# Exoskeleton_PCB_v2.net
KiCad netlist of a schematic drawn in EAGLE
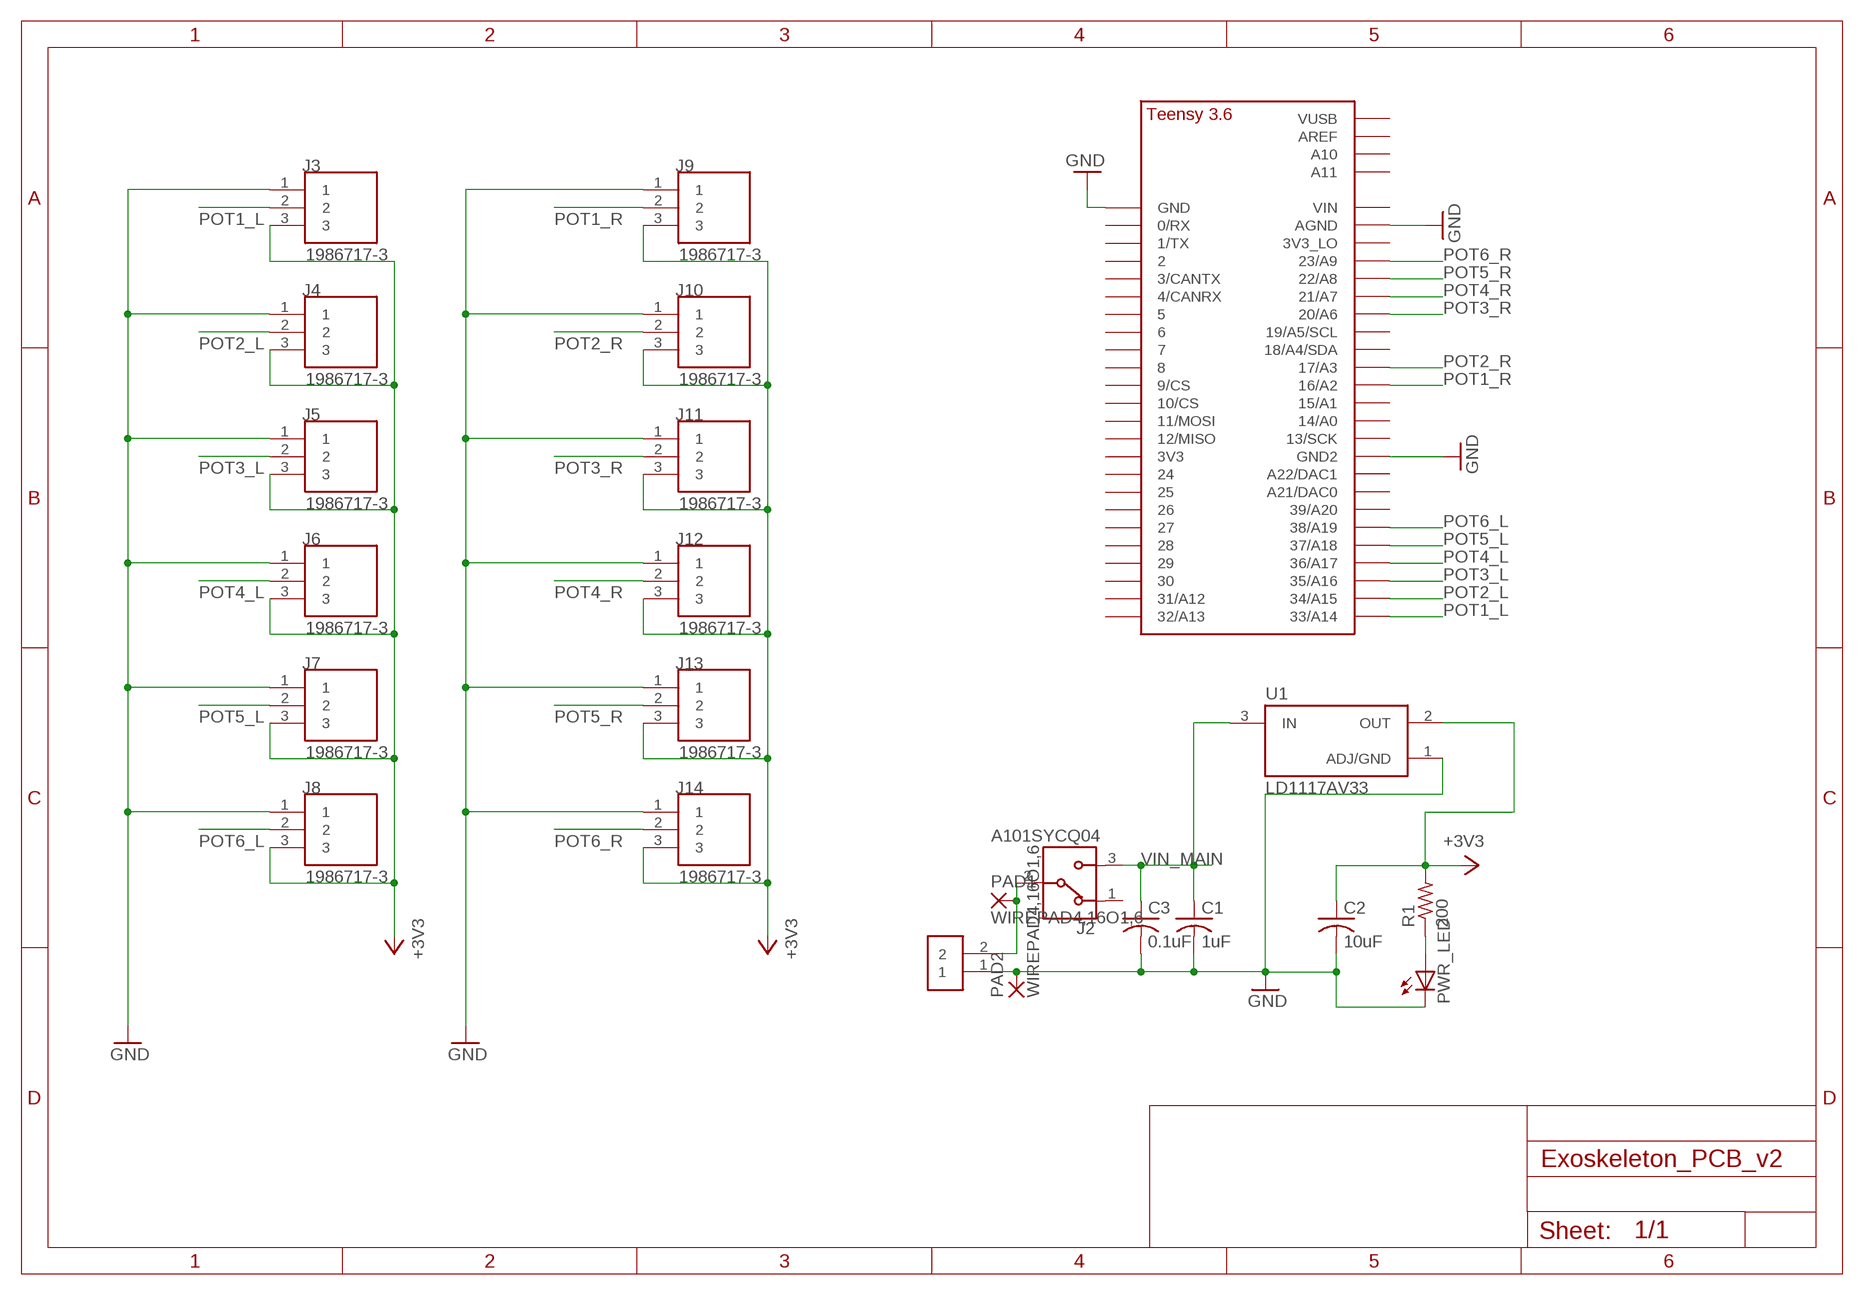
[diagram p0: schematic, sheet 1]

(export (version "E")
  (design (tool "Eeschema 10.0.6"))
  (components
    (comp (ref "C1")
      (value "1uF")
      (footprint "eagle-import:C050-030X075")
      (libsource (lib "eagle-import") (part "C-US050-030X075"))
    )
    (comp (ref "C2")
      (value "10uF")
      (footprint "eagle-import:C050-030X075")
      (libsource (lib "eagle-import") (part "C-US050-030X075"))
    )
    (comp (ref "C3")
      (value "0.1uF")
      (footprint "eagle-import:C050-030X075")
      (libsource (lib "eagle-import") (part "C-US050-030X075"))
    )
    (comp (ref "J1")
      (value "282837-2")
      (footprint "eagle-import:TE_282837-2")
      (fields (field (name "MF") "TE Connectivity"))
      (libsource (lib "eagle-import") (part "282837-2"))
    )
    (comp (ref "J2")
      (value "A101SYCQ04")
      (footprint "eagle-import:TE_A101SYCQ04")
      (fields (field (name "COMMENT") "4-1825136-5") (field (name "MF") "TE Connectivity"))
      (libsource (lib "eagle-import") (part "A101SYCQ04"))
    )
    (comp (ref "J3")
      (value "1986717-3")
      (footprint "eagle-import:TE_1986717-3")
      (fields (field (name "MF") "TE Connectivity"))
      (libsource (lib "eagle-import") (part "1986717-3"))
    )
    (comp (ref "J4")
      (value "1986717-3")
      (footprint "eagle-import:TE_1986717-3")
      (fields (field (name "MF") "TE Connectivity"))
      (libsource (lib "eagle-import") (part "1986717-3"))
    )
    (comp (ref "J5")
      (value "1986717-3")
      (footprint "eagle-import:TE_1986717-3")
      (fields (field (name "MF") "TE Connectivity"))
      (libsource (lib "eagle-import") (part "1986717-3"))
    )
    (comp (ref "J6")
      (value "1986717-3")
      (footprint "eagle-import:TE_1986717-3")
      (fields (field (name "MF") "TE Connectivity"))
      (libsource (lib "eagle-import") (part "1986717-3"))
    )
    (comp (ref "J7")
      (value "1986717-3")
      (footprint "eagle-import:TE_1986717-3")
      (fields (field (name "MF") "TE Connectivity"))
      (libsource (lib "eagle-import") (part "1986717-3"))
    )
    (comp (ref "J8")
      (value "1986717-3")
      (footprint "eagle-import:TE_1986717-3")
      (fields (field (name "MF") "TE Connectivity"))
      (libsource (lib "eagle-import") (part "1986717-3"))
    )
    (comp (ref "J9")
      (value "1986717-3")
      (footprint "eagle-import:TE_1986717-3")
      (fields (field (name "MF") "TE Connectivity"))
      (libsource (lib "eagle-import") (part "1986717-3"))
    )
    (comp (ref "J10")
      (value "1986717-3")
      (footprint "eagle-import:TE_1986717-3")
      (fields (field (name "MF") "TE Connectivity"))
      (libsource (lib "eagle-import") (part "1986717-3"))
    )
    (comp (ref "J11")
      (value "1986717-3")
      (footprint "eagle-import:TE_1986717-3")
      (fields (field (name "MF") "TE Connectivity"))
      (libsource (lib "eagle-import") (part "1986717-3"))
    )
    (comp (ref "J12")
      (value "1986717-3")
      (footprint "eagle-import:TE_1986717-3")
      (fields (field (name "MF") "TE Connectivity"))
      (libsource (lib "eagle-import") (part "1986717-3"))
    )
    (comp (ref "J13")
      (value "1986717-3")
      (footprint "eagle-import:TE_1986717-3")
      (fields (field (name "MF") "TE Connectivity"))
      (libsource (lib "eagle-import") (part "1986717-3"))
    )
    (comp (ref "J14")
      (value "1986717-3")
      (footprint "eagle-import:TE_1986717-3")
      (fields (field (name "MF") "TE Connectivity"))
      (libsource (lib "eagle-import") (part "1986717-3"))
    )
    (comp (ref "PAD1")
      (value "WIREPAD4,16O1,6")
      (footprint "eagle-import:4,16O1,6")
      (libsource (lib "eagle-import") (part "WIREPAD4,16O1,6"))
    )
    (comp (ref "PAD2")
      (value "WIREPAD4,16O1,6")
      (footprint "eagle-import:4,16O1,6")
      (libsource (lib "eagle-import") (part "WIREPAD4,16O1,6"))
    )
    (comp (ref "PWR_LED")
      (value "LED5MM")
      (footprint "eagle-import:LED5MM")
      (libsource (lib "eagle-import") (part "LED5MM"))
    )
    (comp (ref "R1")
      (value "200")
      (footprint "eagle-import:0207_9")
      (libsource (lib "eagle-import") (part "R-US_0207/9"))
    )
    (comp (ref "U$1")
      (value "TEENSY_3.5/3.6_BASIC")
      (footprint "eagle-import:TEENSY_3.5_3.6_BASIC")
      (libsource (lib "eagle-import") (part "TEENSY_3.5/3.6_BASIC"))
    )
    (comp (ref "U1")
      (value "LD1117AV33")
      (footprint "eagle-import:TO255P1020X450X1968-3")
      (fields (field (name "MF") "STMicroelectronics"))
      (libsource (lib "eagle-import") (part "LD1117AV33"))
    )
  )
  (nets
    (net (code "1") (name "+3V3") (class "Default")
      (node (ref "C2") (pin "1") (pinfunction "1_1") (pintype "passive"))
      (node (ref "J10") (pin "3") (pinfunction "3_3") (pintype "passive"))
      (node (ref "J11") (pin "3") (pinfunction "3_3") (pintype "passive"))
      (node (ref "J12") (pin "3") (pinfunction "3_3") (pintype "passive"))
      (node (ref "J13") (pin "3") (pinfunction "3_3") (pintype "passive"))
      (node (ref "J14") (pin "3") (pinfunction "3_3") (pintype "passive"))
      (node (ref "J3") (pin "3") (pinfunction "3_3") (pintype "passive"))
      (node (ref "J4") (pin "3") (pinfunction "3_3") (pintype "passive"))
      (node (ref "J5") (pin "3") (pinfunction "3_3") (pintype "passive"))
      (node (ref "J6") (pin "3") (pinfunction "3_3") (pintype "passive"))
      (node (ref "J7") (pin "3") (pinfunction "3_3") (pintype "passive"))
      (node (ref "J8") (pin "3") (pinfunction "3_3") (pintype "passive"))
      (node (ref "J9") (pin "3") (pinfunction "3_3") (pintype "passive"))
      (node (ref "R1") (pin "2") (pinfunction "2_2") (pintype "passive"))
      (node (ref "U1") (pin "2") (pinfunction "OUT_2") (pintype "output"))
    )
    (net (code "2") (name "/POT1_L") (class "Default")
      (node (ref "J3") (pin "2") (pinfunction "2_2") (pintype "passive"))
      (node (ref "U$1") (pin "33/A14") (pinfunction "33/A14_33/A14") (pintype "bidirectional"))
    )
    (net (code "3") (name "/POT1_R") (class "Default")
      (node (ref "J9") (pin "2") (pinfunction "2_2") (pintype "passive"))
      (node (ref "U$1") (pin "16/A2") (pinfunction "16/A2_16/A2") (pintype "bidirectional"))
    )
    (net (code "4") (name "/POT2_L") (class "Default")
      (node (ref "J4") (pin "2") (pinfunction "2_2") (pintype "passive"))
      (node (ref "U$1") (pin "34/A15") (pinfunction "34/A15_34/A15") (pintype "bidirectional"))
    )
    (net (code "5") (name "/POT2_R") (class "Default")
      (node (ref "J10") (pin "2") (pinfunction "2_2") (pintype "passive"))
      (node (ref "U$1") (pin "17/A3") (pinfunction "17/A3_17/A3") (pintype "bidirectional"))
    )
    (net (code "6") (name "/POT3_L") (class "Default")
      (node (ref "J5") (pin "2") (pinfunction "2_2") (pintype "passive"))
      (node (ref "U$1") (pin "35/A16") (pinfunction "35/A16_35/A16") (pintype "bidirectional"))
    )
    (net (code "7") (name "/POT3_R") (class "Default")
      (node (ref "J11") (pin "2") (pinfunction "2_2") (pintype "passive"))
      (node (ref "U$1") (pin "20/A6") (pinfunction "20/A6_20/A6") (pintype "bidirectional"))
    )
    (net (code "8") (name "/POT4_L") (class "Default")
      (node (ref "J6") (pin "2") (pinfunction "2_2") (pintype "passive"))
      (node (ref "U$1") (pin "36/A17") (pinfunction "36/A17_36/A17") (pintype "bidirectional"))
    )
    (net (code "9") (name "/POT4_R") (class "Default")
      (node (ref "J12") (pin "2") (pinfunction "2_2") (pintype "passive"))
      (node (ref "U$1") (pin "21/A7") (pinfunction "21/A7_21/A7") (pintype "bidirectional"))
    )
    (net (code "10") (name "/POT5_L") (class "Default")
      (node (ref "J7") (pin "2") (pinfunction "2_2") (pintype "passive"))
      (node (ref "U$1") (pin "37/A18") (pinfunction "37/A18_37/A18") (pintype "bidirectional"))
    )
    (net (code "11") (name "/POT5_R") (class "Default")
      (node (ref "J13") (pin "2") (pinfunction "2_2") (pintype "passive"))
      (node (ref "U$1") (pin "22/A8") (pinfunction "22/A8_22/A8") (pintype "bidirectional"))
    )
    (net (code "12") (name "/POT6_L") (class "Default")
      (node (ref "J8") (pin "2") (pinfunction "2_2") (pintype "passive"))
      (node (ref "U$1") (pin "38/A19") (pinfunction "38/A19_38/A19") (pintype "bidirectional"))
    )
    (net (code "13") (name "/POT6_R") (class "Default")
      (node (ref "J14") (pin "2") (pinfunction "2_2") (pintype "passive"))
      (node (ref "U$1") (pin "23/A9") (pinfunction "23/A9_23/A9") (pintype "bidirectional"))
    )
    (net (code "14") (name "/VIN_MAIN") (class "Default")
      (node (ref "C1") (pin "1") (pinfunction "1_1") (pintype "passive"))
      (node (ref "C3") (pin "1") (pinfunction "1_1") (pintype "passive"))
      (node (ref "J2") (pin "3") (pinfunction "3_3") (pintype "passive"))
      (node (ref "U1") (pin "3") (pinfunction "IN_3") (pintype "input"))
    )
    (net (code "15") (name "GND") (class "Default")
      (node (ref "C1") (pin "2") (pinfunction "2_2") (pintype "passive"))
      (node (ref "C2") (pin "2") (pinfunction "2_2") (pintype "passive"))
      (node (ref "C3") (pin "2") (pinfunction "2_2") (pintype "passive"))
      (node (ref "J1") (pin "1") (pinfunction "1_1") (pintype "passive"))
      (node (ref "J10") (pin "1") (pinfunction "1_1") (pintype "passive"))
      (node (ref "J11") (pin "1") (pinfunction "1_1") (pintype "passive"))
      (node (ref "J12") (pin "1") (pinfunction "1_1") (pintype "passive"))
      (node (ref "J13") (pin "1") (pinfunction "1_1") (pintype "passive"))
      (node (ref "J14") (pin "1") (pinfunction "1_1") (pintype "passive"))
      (node (ref "J3") (pin "1") (pinfunction "1_1") (pintype "passive"))
      (node (ref "J4") (pin "1") (pinfunction "1_1") (pintype "passive"))
      (node (ref "J5") (pin "1") (pinfunction "1_1") (pintype "passive"))
      (node (ref "J6") (pin "1") (pinfunction "1_1") (pintype "passive"))
      (node (ref "J7") (pin "1") (pinfunction "1_1") (pintype "passive"))
      (node (ref "J8") (pin "1") (pinfunction "1_1") (pintype "passive"))
      (node (ref "J9") (pin "1") (pinfunction "1_1") (pintype "passive"))
      (node (ref "PAD2") (pin "1") (pinfunction "P_1") (pintype "passive"))
      (node (ref "PWR_LED") (pin "K") (pinfunction "C_K") (pintype "passive"))
      (node (ref "U$1") (pin "AGND") (pinfunction "AGND_AGND") (pintype "bidirectional"))
      (node (ref "U$1") (pin "GND") (pinfunction "GND_GND") (pintype "bidirectional"))
      (node (ref "U$1") (pin "GND2") (pinfunction "GND2_GND2") (pintype "bidirectional"))
      (node (ref "U1") (pin "1") (pinfunction "ADJ/GND_1") (pintype "passive"))
    )
    (net (code "16") (name "Net-(PAD1-P)") (class "Default")
      (node (ref "J1") (pin "2") (pinfunction "2_2") (pintype "passive"))
      (node (ref "J2") (pin "2") (pinfunction "2_2") (pintype "passive"))
      (node (ref "PAD1") (pin "1") (pinfunction "P_1") (pintype "passive"))
    )
    (net (code "17") (name "Net-(PWR_LED-PadA)") (class "Default")
      (node (ref "PWR_LED") (pin "A") (pinfunction "A_A") (pintype "passive"))
      (node (ref "R1") (pin "1") (pinfunction "1_1") (pintype "passive"))
    )
    (net (code "18") (name "unconnected-(J2-Pad1)") (class "Default")
      (node (ref "J2") (pin "1") (pinfunction "1_1") (pintype "passive"))
    )
    (net (code "19") (name "unconnected-(U$1-A21{slash}DAC0-Pad21{slash}DAC0)") (class "Default")
      (node (ref "U$1") (pin "21/DAC0") (pinfunction "A21/DAC0_21/DAC0") (pintype "bidirectional"))
    )
    (net (code "20") (name "unconnected-(U$1-Pad0{slash}RX)") (class "Default")
      (node (ref "U$1") (pin "0/RX") (pinfunction "0/RX_0/RX") (pintype "bidirectional"))
    )
    (net (code "21") (name "unconnected-(U$1-Pad1{slash}TX)") (class "Default")
      (node (ref "U$1") (pin "1/TX") (pinfunction "1/TX_1/TX") (pintype "bidirectional"))
    )
    (net (code "22") (name "unconnected-(U$1-Pad2)") (class "Default")
      (node (ref "U$1") (pin "2") (pinfunction "2_2") (pintype "bidirectional"))
    )
    (net (code "23") (name "unconnected-(U$1-Pad3V3)") (class "Default")
      (node (ref "U$1") (pin "3V3") (pinfunction "3V3_3V3") (pintype "bidirectional"))
    )
    (net (code "24") (name "unconnected-(U$1-Pad3V3_LO)") (class "Default")
      (node (ref "U$1") (pin "3V3_LO") (pinfunction "3V3_LO_3V3_LO") (pintype "bidirectional"))
    )
    (net (code "25") (name "unconnected-(U$1-Pad3{slash}CANTX)") (class "Default")
      (node (ref "U$1") (pin "3/CANTX") (pinfunction "3/CANTX_3/CANTX") (pintype "bidirectional"))
    )
    (net (code "26") (name "unconnected-(U$1-Pad4{slash}CANRX)") (class "Default")
      (node (ref "U$1") (pin "4/CANRX") (pinfunction "4/CANRX_4/CANRX") (pintype "bidirectional"))
    )
    (net (code "27") (name "unconnected-(U$1-Pad5)") (class "Default")
      (node (ref "U$1") (pin "5") (pinfunction "5_5") (pintype "bidirectional"))
    )
    (net (code "28") (name "unconnected-(U$1-Pad6)") (class "Default")
      (node (ref "U$1") (pin "6") (pinfunction "6_6") (pintype "bidirectional"))
    )
    (net (code "29") (name "unconnected-(U$1-Pad7)") (class "Default")
      (node (ref "U$1") (pin "7") (pinfunction "7_7") (pintype "bidirectional"))
    )
    (net (code "30") (name "unconnected-(U$1-Pad8)") (class "Default")
      (node (ref "U$1") (pin "8") (pinfunction "8_8") (pintype "bidirectional"))
    )
    (net (code "31") (name "unconnected-(U$1-Pad9{slash}CS)") (class "Default")
      (node (ref "U$1") (pin "9/CS") (pinfunction "9/CS_9/CS") (pintype "bidirectional"))
    )
    (net (code "32") (name "unconnected-(U$1-Pad10{slash}CS)") (class "Default")
      (node (ref "U$1") (pin "10/CS") (pinfunction "10/CS_10/CS") (pintype "bidirectional"))
    )
    (net (code "33") (name "unconnected-(U$1-Pad11{slash}MOSI)") (class "Default")
      (node (ref "U$1") (pin "11/MOSI") (pinfunction "11/MOSI_11/MOSI") (pintype "bidirectional"))
    )
    (net (code "34") (name "unconnected-(U$1-Pad12{slash}MISO)") (class "Default")
      (node (ref "U$1") (pin "12/MISO") (pinfunction "12/MISO_12/MISO") (pintype "bidirectional"))
    )
    (net (code "35") (name "unconnected-(U$1-Pad13{slash}SCK)") (class "Default")
      (node (ref "U$1") (pin "13/SCK") (pinfunction "13/SCK_13/SCK") (pintype "bidirectional"))
    )
    (net (code "36") (name "unconnected-(U$1-Pad14{slash}A0)") (class "Default")
      (node (ref "U$1") (pin "14/A0") (pinfunction "14/A0_14/A0") (pintype "bidirectional"))
    )
    (net (code "37") (name "unconnected-(U$1-Pad15{slash}A1)") (class "Default")
      (node (ref "U$1") (pin "15/A1") (pinfunction "15/A1_15/A1") (pintype "bidirectional"))
    )
    (net (code "38") (name "unconnected-(U$1-Pad18{slash}A4{slash}SDA)") (class "Default")
      (node (ref "U$1") (pin "18/A4/SDA") (pinfunction "18/A4/SDA_18/A4/SDA") (pintype "bidirectional"))
    )
    (net (code "39") (name "unconnected-(U$1-Pad19{slash}A5{slash}SCL)") (class "Default")
      (node (ref "U$1") (pin "19/A5/SCL") (pinfunction "19/A5/SCL_19/A5/SCL") (pintype "bidirectional"))
    )
    (net (code "40") (name "unconnected-(U$1-Pad24)") (class "Default")
      (node (ref "U$1") (pin "24") (pinfunction "24_24") (pintype "bidirectional"))
    )
    (net (code "41") (name "unconnected-(U$1-Pad25)") (class "Default")
      (node (ref "U$1") (pin "25") (pinfunction "25_25") (pintype "bidirectional"))
    )
    (net (code "42") (name "unconnected-(U$1-Pad26)") (class "Default")
      (node (ref "U$1") (pin "26") (pinfunction "26_26") (pintype "bidirectional"))
    )
    (net (code "43") (name "unconnected-(U$1-Pad27)") (class "Default")
      (node (ref "U$1") (pin "27") (pinfunction "27_27") (pintype "bidirectional"))
    )
    (net (code "44") (name "unconnected-(U$1-Pad28)") (class "Default")
      (node (ref "U$1") (pin "28") (pinfunction "28_28") (pintype "bidirectional"))
    )
    (net (code "45") (name "unconnected-(U$1-Pad29)") (class "Default")
      (node (ref "U$1") (pin "29") (pinfunction "29_29") (pintype "bidirectional"))
    )
    (net (code "46") (name "unconnected-(U$1-Pad30)") (class "Default")
      (node (ref "U$1") (pin "30") (pinfunction "30_30") (pintype "bidirectional"))
    )
    (net (code "47") (name "unconnected-(U$1-Pad31{slash}A12)") (class "Default")
      (node (ref "U$1") (pin "31/A12") (pinfunction "31/A12_31/A12") (pintype "bidirectional"))
    )
    (net (code "48") (name "unconnected-(U$1-Pad32{slash}A13)") (class "Default")
      (node (ref "U$1") (pin "32/A13") (pinfunction "32/A13_32/A13") (pintype "bidirectional"))
    )
    (net (code "49") (name "unconnected-(U$1-Pad39{slash}A20)") (class "Default")
      (node (ref "U$1") (pin "39/A20") (pinfunction "39/A20_39/A20") (pintype "bidirectional"))
    )
    (net (code "50") (name "unconnected-(U$1-PadA10)") (class "Default")
      (node (ref "U$1") (pin "A10") (pinfunction "A10_A10") (pintype "bidirectional"))
    )
    (net (code "51") (name "unconnected-(U$1-PadA11)") (class "Default")
      (node (ref "U$1") (pin "A11") (pinfunction "A11_A11") (pintype "bidirectional"))
    )
    (net (code "52") (name "unconnected-(U$1-PadA22{slash}DAC1)") (class "Default")
      (node (ref "U$1") (pin "A22/DAC1") (pinfunction "A22/DAC1_A22/DAC1") (pintype "bidirectional"))
    )
    (net (code "53") (name "unconnected-(U$1-PadAREF)") (class "Default")
      (node (ref "U$1") (pin "AREF") (pinfunction "AREF_AREF") (pintype "bidirectional"))
    )
    (net (code "54") (name "unconnected-(U$1-PadVIN)") (class "Default")
      (node (ref "U$1") (pin "VIN") (pinfunction "VIN_VIN") (pintype "bidirectional"))
    )
    (net (code "55") (name "unconnected-(U$1-PadVUSB)") (class "Default")
      (node (ref "U$1") (pin "VUSB") (pinfunction "VUSB_VUSB") (pintype "bidirectional"))
    )
  )
)
